# root.net
KiCad netlist of a schematic drawn in EAGLE
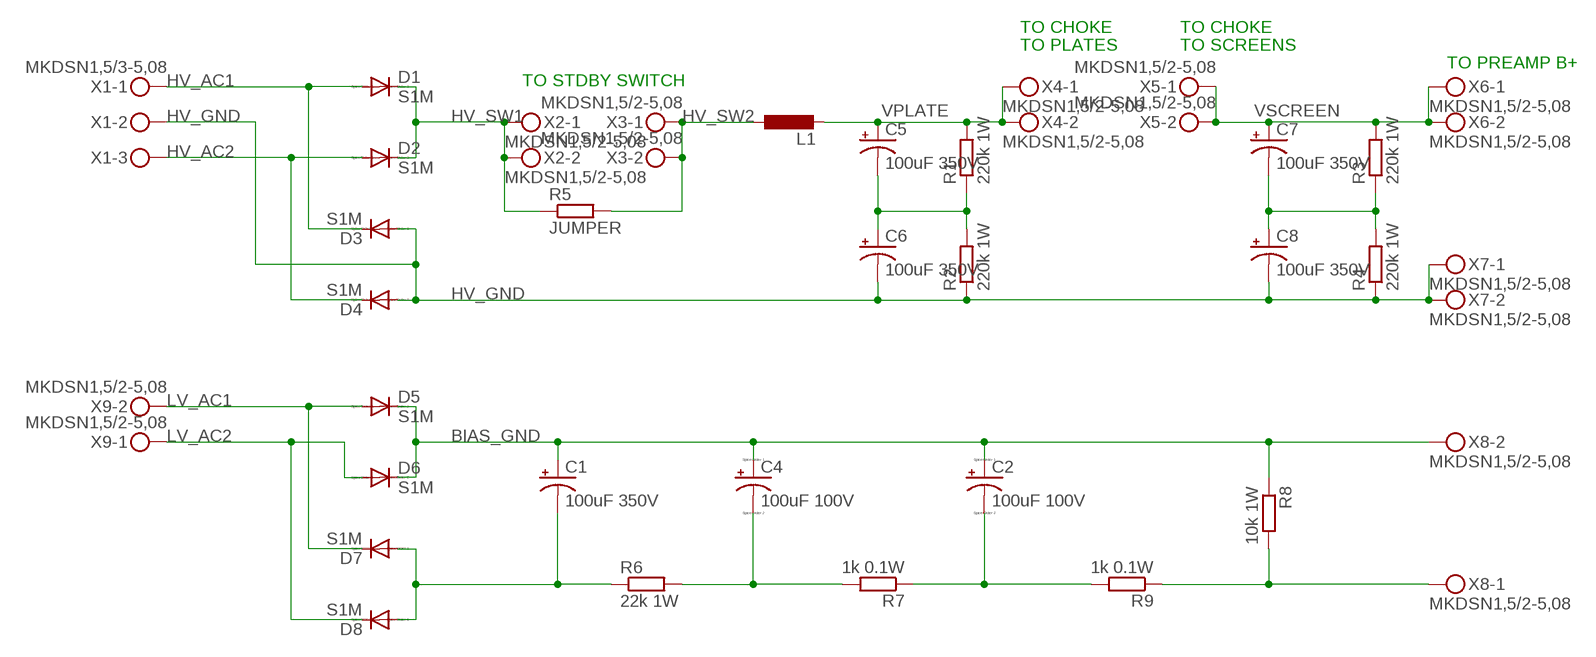
[diagram p0: schematic, sheet 1]

(export (version "E")
  (design (tool "Eeschema 10.0.6"))
  (components
    (comp (ref "C1")
      (value "100uF 350V")
      (footprint "eagle-import:E7,5-18")
      (libsource (lib "eagle-import") (part "CPOL-USE7.5-18"))
    )
    (comp (ref "C2")
      (value "100uF 100V")
      (footprint "eagle-import:PANASONIC_F")
      (libsource (lib "eagle-import") (part "resistor_CPOL-USF"))
    )
    (comp (ref "C4")
      (value "100uF 100V")
      (footprint "eagle-import:PANASONIC_F")
      (libsource (lib "eagle-import") (part "resistor_CPOL-USF"))
    )
    (comp (ref "C5")
      (value "100uF 350V")
      (footprint "eagle-import:E7,5-18")
      (libsource (lib "eagle-import") (part "CPOL-USE7.5-18"))
    )
    (comp (ref "C6")
      (value "100uF 350V")
      (footprint "eagle-import:E7,5-18")
      (libsource (lib "eagle-import") (part "CPOL-USE7.5-18"))
    )
    (comp (ref "C7")
      (value "100uF 350V")
      (footprint "eagle-import:E7,5-18")
      (libsource (lib "eagle-import") (part "CPOL-USE7.5-18"))
    )
    (comp (ref "C8")
      (value "100uF 350V")
      (footprint "eagle-import:E7,5-18")
      (libsource (lib "eagle-import") (part "CPOL-USE7.5-18"))
    )
    (comp (ref "D1")
      (value "S1M")
      (footprint "eagle-import:SMA")
      (libsource (lib "eagle-import") (part "S1M"))
    )
    (comp (ref "D2")
      (value "S1M")
      (footprint "eagle-import:SMA")
      (libsource (lib "eagle-import") (part "S1M"))
    )
    (comp (ref "D3")
      (value "S1M")
      (footprint "eagle-import:SMA")
      (libsource (lib "eagle-import") (part "S1M"))
    )
    (comp (ref "D4")
      (value "S1M")
      (footprint "eagle-import:SMA")
      (libsource (lib "eagle-import") (part "S1M"))
    )
    (comp (ref "D5")
      (value "S1M")
      (footprint "eagle-import:SMA")
      (libsource (lib "eagle-import") (part "S1M"))
    )
    (comp (ref "D6")
      (value "S1M")
      (footprint "eagle-import:SMA")
      (libsource (lib "eagle-import") (part "S1M"))
    )
    (comp (ref "D7")
      (value "S1M")
      (footprint "eagle-import:SMA")
      (libsource (lib "eagle-import") (part "S1M"))
    )
    (comp (ref "D8")
      (value "S1M")
      (footprint "eagle-import:SMA")
      (libsource (lib "eagle-import") (part "S1M"))
    )
    (comp (ref "L1")
      (value "L-EUL4516C")
      (footprint "eagle-import:L4516C")
      (libsource (lib "eagle-import") (part "L-EUL4516C"))
    )
    (comp (ref "R1")
      (value "220k 1W")
      (footprint "eagle-import:R2512")
      (libsource (lib "eagle-import") (part "R-EU_R2512"))
    )
    (comp (ref "R2")
      (value "220k 1W")
      (footprint "eagle-import:R2512")
      (libsource (lib "eagle-import") (part "R-EU_R2512"))
    )
    (comp (ref "R3")
      (value "220k 1W")
      (footprint "eagle-import:R2512")
      (libsource (lib "eagle-import") (part "R-EU_R2512"))
    )
    (comp (ref "R4")
      (value "220k 1W")
      (footprint "eagle-import:R2512")
      (libsource (lib "eagle-import") (part "R-EU_R2512"))
    )
    (comp (ref "R5")
      (value "JUMPER")
      (footprint "eagle-import:R1206")
      (libsource (lib "eagle-import") (part "resistor_R-EU_R1206"))
    )
    (comp (ref "R6")
      (value "22k 1W")
      (footprint "eagle-import:R2512")
      (libsource (lib "eagle-import") (part "R-EU_R2512"))
    )
    (comp (ref "R7")
      (value "1k 0.1W")
      (footprint "eagle-import:R0603")
      (libsource (lib "eagle-import") (part "resistor_R-EU_R0603"))
    )
    (comp (ref "R8")
      (value "10k 1W")
      (footprint "eagle-import:R2512")
      (libsource (lib "eagle-import") (part "R-EU_R2512"))
    )
    (comp (ref "R9")
      (value "1k 0.1W")
      (footprint "eagle-import:R0603")
      (libsource (lib "eagle-import") (part "resistor_R-EU_R0603"))
    )
    (comp (ref "X1")
      (value "MKDSN1,5/3-5,08")
      (footprint "eagle-import:MKDSN1,5_3-5,08")
      (libsource (lib "eagle-import") (part "MKDSN1,5/3-5,08"))
    )
    (comp (ref "X2")
      (value "MKDSN1,5/2-5,08")
      (footprint "eagle-import:MKDSN1,5_2-5,08")
      (libsource (lib "eagle-import") (part "MKDSN1,5/2-5,08"))
    )
    (comp (ref "X3")
      (value "MKDSN1,5/2-5,08")
      (footprint "eagle-import:MKDSN1,5_2-5,08")
      (libsource (lib "eagle-import") (part "MKDSN1,5/2-5,08"))
    )
    (comp (ref "X4")
      (value "MKDSN1,5/2-5,08")
      (footprint "eagle-import:MKDSN1,5_2-5,08")
      (libsource (lib "eagle-import") (part "MKDSN1,5/2-5,08"))
    )
    (comp (ref "X5")
      (value "MKDSN1,5/2-5,08")
      (footprint "eagle-import:MKDSN1,5_2-5,08")
      (libsource (lib "eagle-import") (part "MKDSN1,5/2-5,08"))
    )
    (comp (ref "X6")
      (value "MKDSN1,5/2-5,08")
      (footprint "eagle-import:MKDSN1,5_2-5,08")
      (libsource (lib "eagle-import") (part "MKDSN1,5/2-5,08"))
    )
    (comp (ref "X7")
      (value "MKDSN1,5/2-5,08")
      (footprint "eagle-import:MKDSN1,5_2-5,08")
      (libsource (lib "eagle-import") (part "MKDSN1,5/2-5,08"))
    )
    (comp (ref "X8")
      (value "MKDSN1,5/2-5,08")
      (footprint "eagle-import:MKDSN1,5_2-5,08")
      (libsource (lib "eagle-import") (part "MKDSN1,5/2-5,08"))
    )
    (comp (ref "X9")
      (value "MKDSN1,5/2-5,08")
      (footprint "eagle-import:MKDSN1,5_2-5,08")
      (libsource (lib "eagle-import") (part "MKDSN1,5/2-5,08"))
    )
  )
  (nets
    (net (code "1") (name "/BIAS_GND") (class "Default")
      (node (ref "C1") (pin "+") (pinfunction "+_+") (pintype "passive"))
      (node (ref "C2") (pin "+") (pinfunction "+_+") (pintype "passive"))
      (node (ref "C4") (pin "+") (pinfunction "+_+") (pintype "passive"))
      (node (ref "D5") (pin "C") (pinfunction "C_C") (pintype "passive"))
      (node (ref "D6") (pin "C") (pinfunction "C_C") (pintype "passive"))
      (node (ref "R8") (pin "1") (pinfunction "1_1") (pintype "passive"))
      (node (ref "X8") (pin "2") (pinfunction "KL_2") (pintype "passive"))
    )
    (net (code "2") (name "/HV_AC1") (class "Default")
      (node (ref "D1") (pin "A") (pinfunction "A_A") (pintype "passive"))
      (node (ref "D3") (pin "C") (pinfunction "C_C") (pintype "passive"))
      (node (ref "X1") (pin "1") (pinfunction "KL_1") (pintype "passive"))
    )
    (net (code "3") (name "/HV_AC2") (class "Default")
      (node (ref "D2") (pin "A") (pinfunction "A_A") (pintype "passive"))
      (node (ref "D4") (pin "C") (pinfunction "C_C") (pintype "passive"))
      (node (ref "X1") (pin "3") (pinfunction "KL_3") (pintype "passive"))
    )
    (net (code "4") (name "/HV_GND") (class "Default")
      (node (ref "C6") (pin "-") (pinfunction "-_-") (pintype "passive"))
      (node (ref "C8") (pin "-") (pinfunction "-_-") (pintype "passive"))
      (node (ref "D3") (pin "A") (pinfunction "A_A") (pintype "passive"))
      (node (ref "D4") (pin "A") (pinfunction "A_A") (pintype "passive"))
      (node (ref "R2") (pin "1") (pinfunction "1_1") (pintype "passive"))
      (node (ref "R4") (pin "1") (pinfunction "1_1") (pintype "passive"))
      (node (ref "X1") (pin "2") (pinfunction "KL_2") (pintype "passive"))
      (node (ref "X7") (pin "1") (pinfunction "KL_1") (pintype "passive"))
      (node (ref "X7") (pin "2") (pinfunction "KL_2") (pintype "passive"))
    )
    (net (code "5") (name "/HV_SW1") (class "Default")
      (node (ref "D1") (pin "C") (pinfunction "C_C") (pintype "passive"))
      (node (ref "D2") (pin "C") (pinfunction "C_C") (pintype "passive"))
      (node (ref "R5") (pin "1") (pinfunction "1_1") (pintype "passive"))
      (node (ref "X2") (pin "1") (pinfunction "KL_1") (pintype "passive"))
      (node (ref "X2") (pin "2") (pinfunction "KL_2") (pintype "passive"))
    )
    (net (code "6") (name "/HV_SW2") (class "Default")
      (node (ref "L1") (pin "1") (pinfunction "1_1") (pintype "passive"))
      (node (ref "R5") (pin "2") (pinfunction "2_2") (pintype "passive"))
      (node (ref "X3") (pin "1") (pinfunction "KL_1") (pintype "passive"))
      (node (ref "X3") (pin "2") (pinfunction "KL_2") (pintype "passive"))
    )
    (net (code "7") (name "/LV_AC1") (class "Default")
      (node (ref "D5") (pin "A") (pinfunction "A_A") (pintype "passive"))
      (node (ref "D7") (pin "C") (pinfunction "C_C") (pintype "passive"))
      (node (ref "X9") (pin "2") (pinfunction "KL_2") (pintype "passive"))
    )
    (net (code "8") (name "/LV_AC2") (class "Default")
      (node (ref "D6") (pin "A") (pinfunction "A_A") (pintype "passive"))
      (node (ref "D8") (pin "C") (pinfunction "C_C") (pintype "passive"))
      (node (ref "X9") (pin "1") (pinfunction "KL_1") (pintype "passive"))
    )
    (net (code "9") (name "/VPLATE") (class "Default")
      (node (ref "C5") (pin "+") (pinfunction "+_+") (pintype "passive"))
      (node (ref "L1") (pin "2") (pinfunction "2_2") (pintype "passive"))
      (node (ref "R1") (pin "2") (pinfunction "2_2") (pintype "passive"))
      (node (ref "X4") (pin "1") (pinfunction "KL_1") (pintype "passive"))
      (node (ref "X4") (pin "2") (pinfunction "KL_2") (pintype "passive"))
    )
    (net (code "10") (name "/VSCREEN") (class "Default")
      (node (ref "C7") (pin "+") (pinfunction "+_+") (pintype "passive"))
      (node (ref "R3") (pin "2") (pinfunction "2_2") (pintype "passive"))
      (node (ref "X5") (pin "1") (pinfunction "KL_1") (pintype "passive"))
      (node (ref "X5") (pin "2") (pinfunction "KL_2") (pintype "passive"))
      (node (ref "X6") (pin "1") (pinfunction "KL_1") (pintype "passive"))
      (node (ref "X6") (pin "2") (pinfunction "KL_2") (pintype "passive"))
    )
    (net (code "11") (name "Net-(C1-Pad-)") (class "Default")
      (node (ref "C1") (pin "-") (pinfunction "-_-") (pintype "passive"))
      (node (ref "D7") (pin "A") (pinfunction "A_A") (pintype "passive"))
      (node (ref "D8") (pin "A") (pinfunction "A_A") (pintype "passive"))
      (node (ref "R6") (pin "1") (pinfunction "1_1") (pintype "passive"))
    )
    (net (code "12") (name "Net-(C2-Pad-)") (class "Default")
      (node (ref "C2") (pin "-") (pinfunction "-_-") (pintype "passive"))
      (node (ref "R7") (pin "1") (pinfunction "1_1") (pintype "passive"))
      (node (ref "R9") (pin "2") (pinfunction "2_2") (pintype "passive"))
    )
    (net (code "13") (name "Net-(C4-Pad-)") (class "Default")
      (node (ref "C4") (pin "-") (pinfunction "-_-") (pintype "passive"))
      (node (ref "R6") (pin "2") (pinfunction "2_2") (pintype "passive"))
      (node (ref "R7") (pin "2") (pinfunction "2_2") (pintype "passive"))
    )
    (net (code "14") (name "Net-(C5-Pad-)") (class "Default")
      (node (ref "C5") (pin "-") (pinfunction "-_-") (pintype "passive"))
      (node (ref "C6") (pin "+") (pinfunction "+_+") (pintype "passive"))
      (node (ref "R1") (pin "1") (pinfunction "1_1") (pintype "passive"))
      (node (ref "R2") (pin "2") (pinfunction "2_2") (pintype "passive"))
    )
    (net (code "15") (name "Net-(C7-Pad-)") (class "Default")
      (node (ref "C7") (pin "-") (pinfunction "-_-") (pintype "passive"))
      (node (ref "C8") (pin "+") (pinfunction "+_+") (pintype "passive"))
      (node (ref "R3") (pin "1") (pinfunction "1_1") (pintype "passive"))
      (node (ref "R4") (pin "2") (pinfunction "2_2") (pintype "passive"))
    )
    (net (code "16") (name "Net-(X8A-KL)") (class "Default")
      (node (ref "R8") (pin "2") (pinfunction "2_2") (pintype "passive"))
      (node (ref "R9") (pin "1") (pinfunction "1_1") (pintype "passive"))
      (node (ref "X8") (pin "1") (pinfunction "KL_1") (pintype "passive"))
    )
  )
)
